# untitled.net
KiCad netlist of a schematic drawn in EAGLE
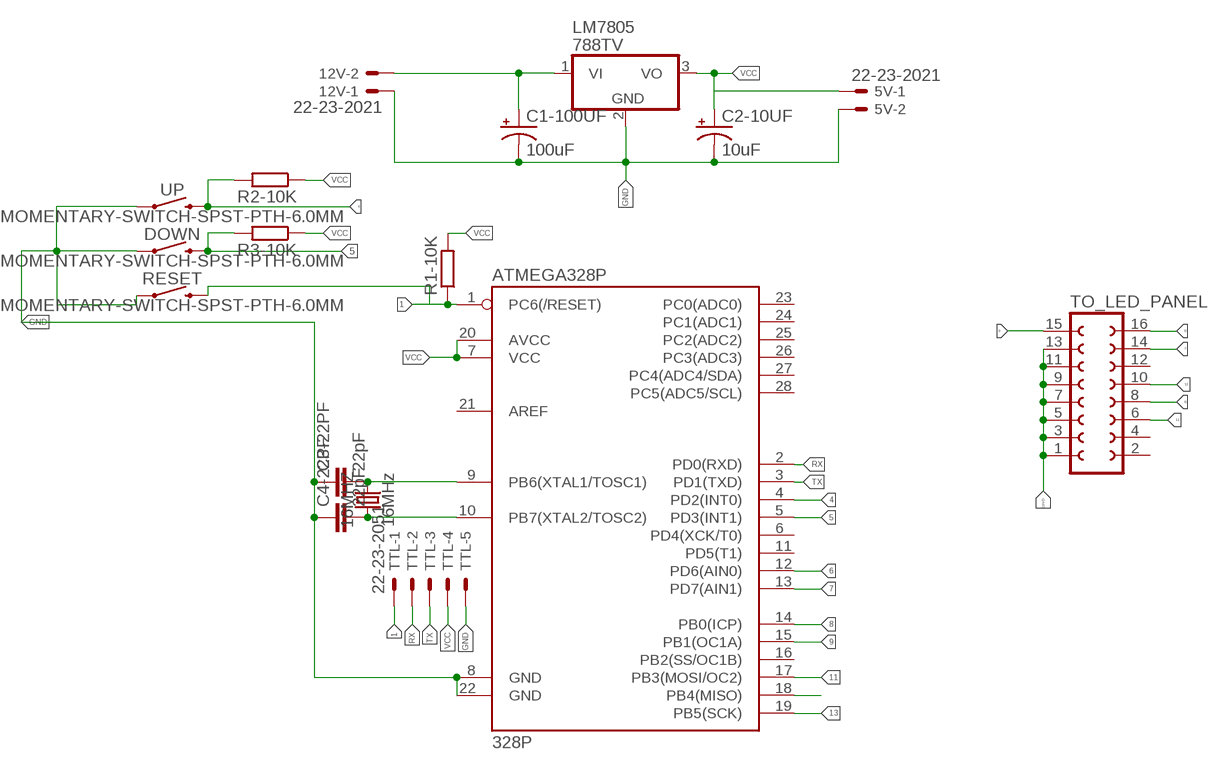
[diagram p0: schematic, sheet 1]

(export (version "E")
  (design (tool "Eeschema 10.0.6"))
  (components
    (comp (ref "5V")
      (value "22-23-2021")
      (footprint "eagle-import:22-23-2021")
      (libsource (lib "eagle-import") (part "22-23-2021"))
    )
    (comp (ref "12V")
      (value "22-23-2021")
      (footprint "eagle-import:22-23-2021")
      (libsource (lib "eagle-import") (part "22-23-2021"))
    )
    (comp (ref "16MHZ")
      (value "16MHz")
      (footprint "eagle-import:HC49US")
      (libsource (lib "eagle-import") (part "CRYSTAL-16MHZPTH-HC49US"))
    )
    (comp (ref "ATMEGA328P")
      (value "328P")
      (footprint "eagle-import:DIP28")
      (libsource (lib "eagle-import") (part "ATMEGA328P_PDIP"))
    )
    (comp (ref "C1-100UF")
      (value "100uF")
      (footprint "eagle-import:CPOL-RADIAL-2.5MM-6.5MM")
      (libsource (lib "eagle-import") (part "100UF-POLAR-RADIAL-2.5MM-25V-20%"))
    )
    (comp (ref "C2-10UF")
      (value "10uF")
      (footprint "eagle-import:CPOL-RADIAL-2.5MM-5MM")
      (libsource (lib "eagle-import") (part "10UF-POLAR-RADIAL-2.5MM-25V-20%"))
    )
    (comp (ref "C3-22PF")
      (value "22pF")
      (footprint "eagle-import:CAP-PTH-2.54")
      (libsource (lib "eagle-import") (part "22PF-PTH-2.54MM-200V-5%"))
    )
    (comp (ref "C4-22PF")
      (value "22pF")
      (footprint "eagle-import:CAP-PTH-2.54")
      (libsource (lib "eagle-import") (part "22PF-PTH-2.54MM-200V-5%"))
    )
    (comp (ref "DOWN")
      (value "MOMENTARY-SWITCH-SPST-PTH-6.0MM")
      (footprint "eagle-import:TACTILE_SWITCH_PTH_6.0MM")
      (libsource (lib "eagle-import") (part "MOMENTARY-SWITCH-SPST-PTH-6.0MM"))
    )
    (comp (ref "LM7805")
      (value "788TV")
      (footprint "eagle-import:TO220V")
      (libsource (lib "eagle-import") (part "78TV8"))
    )
    (comp (ref "R1-10K")
      (value "R-EU_0207/10")
      (footprint "eagle-import:0207_10")
      (libsource (lib "eagle-import") (part "R-EU_0207/10"))
    )
    (comp (ref "R2-10K")
      (value "R-EU_0207/10")
      (footprint "eagle-import:0207_10")
      (libsource (lib "eagle-import") (part "R-EU_0207/10"))
    )
    (comp (ref "R3-10K")
      (value "R-EU_0207/10")
      (footprint "eagle-import:0207_10")
      (libsource (lib "eagle-import") (part "R-EU_0207/10"))
    )
    (comp (ref "RESET")
      (value "MOMENTARY-SWITCH-SPST-PTH-6.0MM")
      (footprint "eagle-import:TACTILE_SWITCH_PTH_6.0MM")
      (libsource (lib "eagle-import") (part "MOMENTARY-SWITCH-SPST-PTH-6.0MM"))
    )
    (comp (ref "TO_LED_PANEL")
      (value "FE08-2")
      (footprint "eagle-import:FE08-2")
      (libsource (lib "eagle-import") (part "FE08-2"))
    )
    (comp (ref "TTL")
      (value "22-23-2051")
      (footprint "eagle-import:22-23-2051")
      (libsource (lib "eagle-import") (part "22-23-2051"))
    )
    (comp (ref "UP")
      (value "MOMENTARY-SWITCH-SPST-PTH-6.0MM")
      (footprint "eagle-import:TACTILE_SWITCH_PTH_6.0MM")
      (libsource (lib "eagle-import") (part "MOMENTARY-SWITCH-SPST-PTH-6.0MM"))
    )
  )
  (nets
    (net (code "1") (name "1") (class "Default")
      (node (ref "ATMEGA328P") (pin "1") (pinfunction "PC6(/RESET)_1") (pintype "bidirectional"))
      (node (ref "R1-10K") (pin "1") (pinfunction "1_1") (pintype "passive"))
      (node (ref "RESET") (pin "3") (pinfunction "2_3") (pintype "passive"))
      (node (ref "TTL") (pin "1") (pinfunction "S_1") (pintype "passive"))
    )
    (net (code "2") (name "4") (class "Default")
      (node (ref "ATMEGA328P") (pin "4") (pinfunction "PD2(INT0)_4") (pintype "bidirectional"))
      (node (ref "R2-10K") (pin "2") (pinfunction "2_2") (pintype "passive"))
      (node (ref "UP") (pin "3") (pinfunction "2_3") (pintype "passive"))
    )
    (net (code "3") (name "5") (class "Default")
      (node (ref "ATMEGA328P") (pin "5") (pinfunction "PD3(INT1)_5") (pintype "bidirectional"))
      (node (ref "DOWN") (pin "3") (pinfunction "2_3") (pintype "passive"))
      (node (ref "R3-10K") (pin "2") (pinfunction "2_2") (pintype "passive"))
    )
    (net (code "4") (name "6") (class "Default")
      (node (ref "ATMEGA328P") (pin "12") (pinfunction "PD6(AIN0)_12") (pintype "bidirectional"))
      (node (ref "TO_LED_PANEL") (pin "16") (pinfunction "16_16") (pintype "passive"))
    )
    (net (code "5") (name "7") (class "Default")
      (node (ref "ATMEGA328P") (pin "13") (pinfunction "PD7(AIN1)_13") (pintype "bidirectional"))
      (node (ref "TO_LED_PANEL") (pin "14") (pinfunction "14_14") (pintype "passive"))
    )
    (net (code "6") (name "8") (class "Default")
      (node (ref "ATMEGA328P") (pin "14") (pinfunction "PB0(ICP)_14") (pintype "bidirectional"))
      (node (ref "TO_LED_PANEL") (pin "8") (pinfunction "8_8") (pintype "passive"))
    )
    (net (code "7") (name "9") (class "Default")
      (node (ref "ATMEGA328P") (pin "15") (pinfunction "PB1(OC1A)_15") (pintype "bidirectional"))
      (node (ref "TO_LED_PANEL") (pin "15") (pinfunction "15_15") (pintype "passive"))
    )
    (net (code "8") (name "11") (class "Default")
      (node (ref "ATMEGA328P") (pin "17") (pinfunction "PB3(MOSI/OC2)_17") (pintype "bidirectional"))
      (node (ref "TO_LED_PANEL") (pin "6") (pinfunction "6_6") (pintype "passive"))
    )
    (net (code "9") (name "13") (class "Default")
      (node (ref "ATMEGA328P") (pin "19") (pinfunction "PB5(SCK)_19") (pintype "bidirectional"))
      (node (ref "TO_LED_PANEL") (pin "10") (pinfunction "10_10") (pintype "passive"))
    )
    (net (code "10") (name "GND") (class "Default")
      (node (ref "12V") (pin "1") (pinfunction "S_1") (pintype "passive"))
      (node (ref "5V") (pin "2") (pinfunction "S_2") (pintype "passive"))
      (node (ref "ATMEGA328P") (pin "22") (pinfunction "GND_22") (pintype "bidirectional"))
      (node (ref "ATMEGA328P") (pin "8") (pinfunction "GND_8") (pintype "bidirectional"))
      (node (ref "C1-100UF") (pin "2") (pinfunction "-_2") (pintype "passive"))
      (node (ref "C2-10UF") (pin "2") (pinfunction "-_2") (pintype "passive"))
      (node (ref "C3-22PF") (pin "1") (pinfunction "1_1") (pintype "passive"))
      (node (ref "C4-22PF") (pin "1") (pinfunction "1_1") (pintype "passive"))
      (node (ref "DOWN") (pin "1") (pinfunction "1_1") (pintype "passive"))
      (node (ref "LM7805") (pin "2") (pinfunction "GND_2") (pintype "passive"))
      (node (ref "RESET") (pin "1") (pinfunction "1_1") (pintype "passive"))
      (node (ref "TO_LED_PANEL") (pin "1") (pinfunction "1_1") (pintype "passive"))
      (node (ref "TO_LED_PANEL") (pin "11") (pinfunction "11_11") (pintype "passive"))
      (node (ref "TO_LED_PANEL") (pin "13") (pinfunction "13_13") (pintype "passive"))
      (node (ref "TO_LED_PANEL") (pin "3") (pinfunction "3_3") (pintype "passive"))
      (node (ref "TO_LED_PANEL") (pin "5") (pinfunction "5_5") (pintype "passive"))
      (node (ref "TO_LED_PANEL") (pin "7") (pinfunction "7_7") (pintype "passive"))
      (node (ref "TO_LED_PANEL") (pin "9") (pinfunction "9_9") (pintype "passive"))
      (node (ref "TTL") (pin "5") (pinfunction "S_5") (pintype "passive"))
      (node (ref "UP") (pin "1") (pinfunction "1_1") (pintype "passive"))
    )
    (net (code "11") (name "Net-(12VB-S)") (class "Default")
      (node (ref "12V") (pin "2") (pinfunction "S_2") (pintype "passive"))
      (node (ref "C1-100UF") (pin "1") (pinfunction "+_1") (pintype "passive"))
      (node (ref "LM7805") (pin "1") (pinfunction "VI_1") (pintype "input"))
    )
    (net (code "12") (name "Net-(ATMEGA328P-PB6(XTAL1{slash}TOSC1))") (class "Default")
      (node (ref "16MHZ") (pin "2") (pinfunction "2_2") (pintype "passive"))
      (node (ref "ATMEGA328P") (pin "9") (pinfunction "PB6(XTAL1/TOSC1)_9") (pintype "bidirectional"))
      (node (ref "C3-22PF") (pin "2") (pinfunction "2_2") (pintype "passive"))
    )
    (net (code "13") (name "Net-(ATMEGA328P-PB7(XTAL2{slash}TOSC2))") (class "Default")
      (node (ref "16MHZ") (pin "1") (pinfunction "1_1") (pintype "passive"))
      (node (ref "ATMEGA328P") (pin "10") (pinfunction "PB7(XTAL2/TOSC2)_10") (pintype "bidirectional"))
      (node (ref "C4-22PF") (pin "2") (pinfunction "2_2") (pintype "passive"))
    )
    (net (code "14") (name "RX") (class "Default")
      (node (ref "ATMEGA328P") (pin "2") (pinfunction "PD0(RXD)_2") (pintype "bidirectional"))
      (node (ref "TTL") (pin "2") (pinfunction "S_2") (pintype "passive"))
    )
    (net (code "15") (name "TX") (class "Default")
      (node (ref "ATMEGA328P") (pin "3") (pinfunction "PD1(TXD)_3") (pintype "bidirectional"))
      (node (ref "TTL") (pin "3") (pinfunction "S_3") (pintype "passive"))
    )
    (net (code "16") (name "VCC") (class "Default")
      (node (ref "5V") (pin "1") (pinfunction "S_1") (pintype "passive"))
      (node (ref "ATMEGA328P") (pin "20") (pinfunction "AVCC_20") (pintype "bidirectional"))
      (node (ref "ATMEGA328P") (pin "7") (pinfunction "VCC_7") (pintype "bidirectional"))
      (node (ref "C2-10UF") (pin "1") (pinfunction "+_1") (pintype "passive"))
      (node (ref "LM7805") (pin "3") (pinfunction "VO_3") (pintype "passive"))
      (node (ref "R1-10K") (pin "2") (pinfunction "2_2") (pintype "passive"))
      (node (ref "R2-10K") (pin "1") (pinfunction "1_1") (pintype "passive"))
      (node (ref "R3-10K") (pin "1") (pinfunction "1_1") (pintype "passive"))
      (node (ref "TTL") (pin "4") (pinfunction "S_4") (pintype "passive"))
    )
    (net (code "17") (name "unconnected-(ATMEGA328P-AREF-Pad21)") (class "Default")
      (node (ref "ATMEGA328P") (pin "21") (pinfunction "AREF_21") (pintype "bidirectional"))
    )
    (net (code "18") (name "unconnected-(ATMEGA328P-PB2(SS{slash}OC1B)-Pad16)") (class "Default")
      (node (ref "ATMEGA328P") (pin "16") (pinfunction "PB2(SS/OC1B)_16") (pintype "bidirectional"))
    )
    (net (code "19") (name "unconnected-(ATMEGA328P-PB4(MISO)-Pad18)") (class "Default")
      (node (ref "ATMEGA328P") (pin "18") (pinfunction "PB4(MISO)_18") (pintype "bidirectional"))
    )
    (net (code "20") (name "unconnected-(ATMEGA328P-PC0(ADC0)-Pad23)") (class "Default")
      (node (ref "ATMEGA328P") (pin "23") (pinfunction "PC0(ADC0)_23") (pintype "bidirectional"))
    )
    (net (code "21") (name "unconnected-(ATMEGA328P-PC1(ADC1)-Pad24)") (class "Default")
      (node (ref "ATMEGA328P") (pin "24") (pinfunction "PC1(ADC1)_24") (pintype "bidirectional"))
    )
    (net (code "22") (name "unconnected-(ATMEGA328P-PC2(ADC2)-Pad25)") (class "Default")
      (node (ref "ATMEGA328P") (pin "25") (pinfunction "PC2(ADC2)_25") (pintype "bidirectional"))
    )
    (net (code "23") (name "unconnected-(ATMEGA328P-PC3(ADC3)-Pad26)") (class "Default")
      (node (ref "ATMEGA328P") (pin "26") (pinfunction "PC3(ADC3)_26") (pintype "bidirectional"))
    )
    (net (code "24") (name "unconnected-(ATMEGA328P-PC4(ADC4{slash}SDA)-Pad27)") (class "Default")
      (node (ref "ATMEGA328P") (pin "27") (pinfunction "PC4(ADC4/SDA)_27") (pintype "bidirectional"))
    )
    (net (code "25") (name "unconnected-(ATMEGA328P-PC5(ADC5{slash}SCL)-Pad28)") (class "Default")
      (node (ref "ATMEGA328P") (pin "28") (pinfunction "PC5(ADC5/SCL)_28") (pintype "bidirectional"))
    )
    (net (code "26") (name "unconnected-(ATMEGA328P-PD4(XCK{slash}T0)-Pad6)") (class "Default")
      (node (ref "ATMEGA328P") (pin "6") (pinfunction "PD4(XCK/T0)_6") (pintype "bidirectional"))
    )
    (net (code "27") (name "unconnected-(ATMEGA328P-PD5(T1)-Pad11)") (class "Default")
      (node (ref "ATMEGA328P") (pin "11") (pinfunction "PD5(T1)_11") (pintype "bidirectional"))
    )
    (net (code "28") (name "unconnected-(TO_LED_PANEL-Pad2)") (class "Default")
      (node (ref "TO_LED_PANEL") (pin "2") (pinfunction "2_2") (pintype "passive"))
    )
    (net (code "29") (name "unconnected-(TO_LED_PANEL-Pad4)") (class "Default")
      (node (ref "TO_LED_PANEL") (pin "4") (pinfunction "4_4") (pintype "passive"))
    )
    (net (code "30") (name "unconnected-(TO_LED_PANEL-Pad12)") (class "Default")
      (node (ref "TO_LED_PANEL") (pin "12") (pinfunction "12_12") (pintype "passive"))
    )
  )
)
